# Schema_plan_b_syntheseproject_V1.net
KiCad netlist of a schematic drawn in EasyEDA
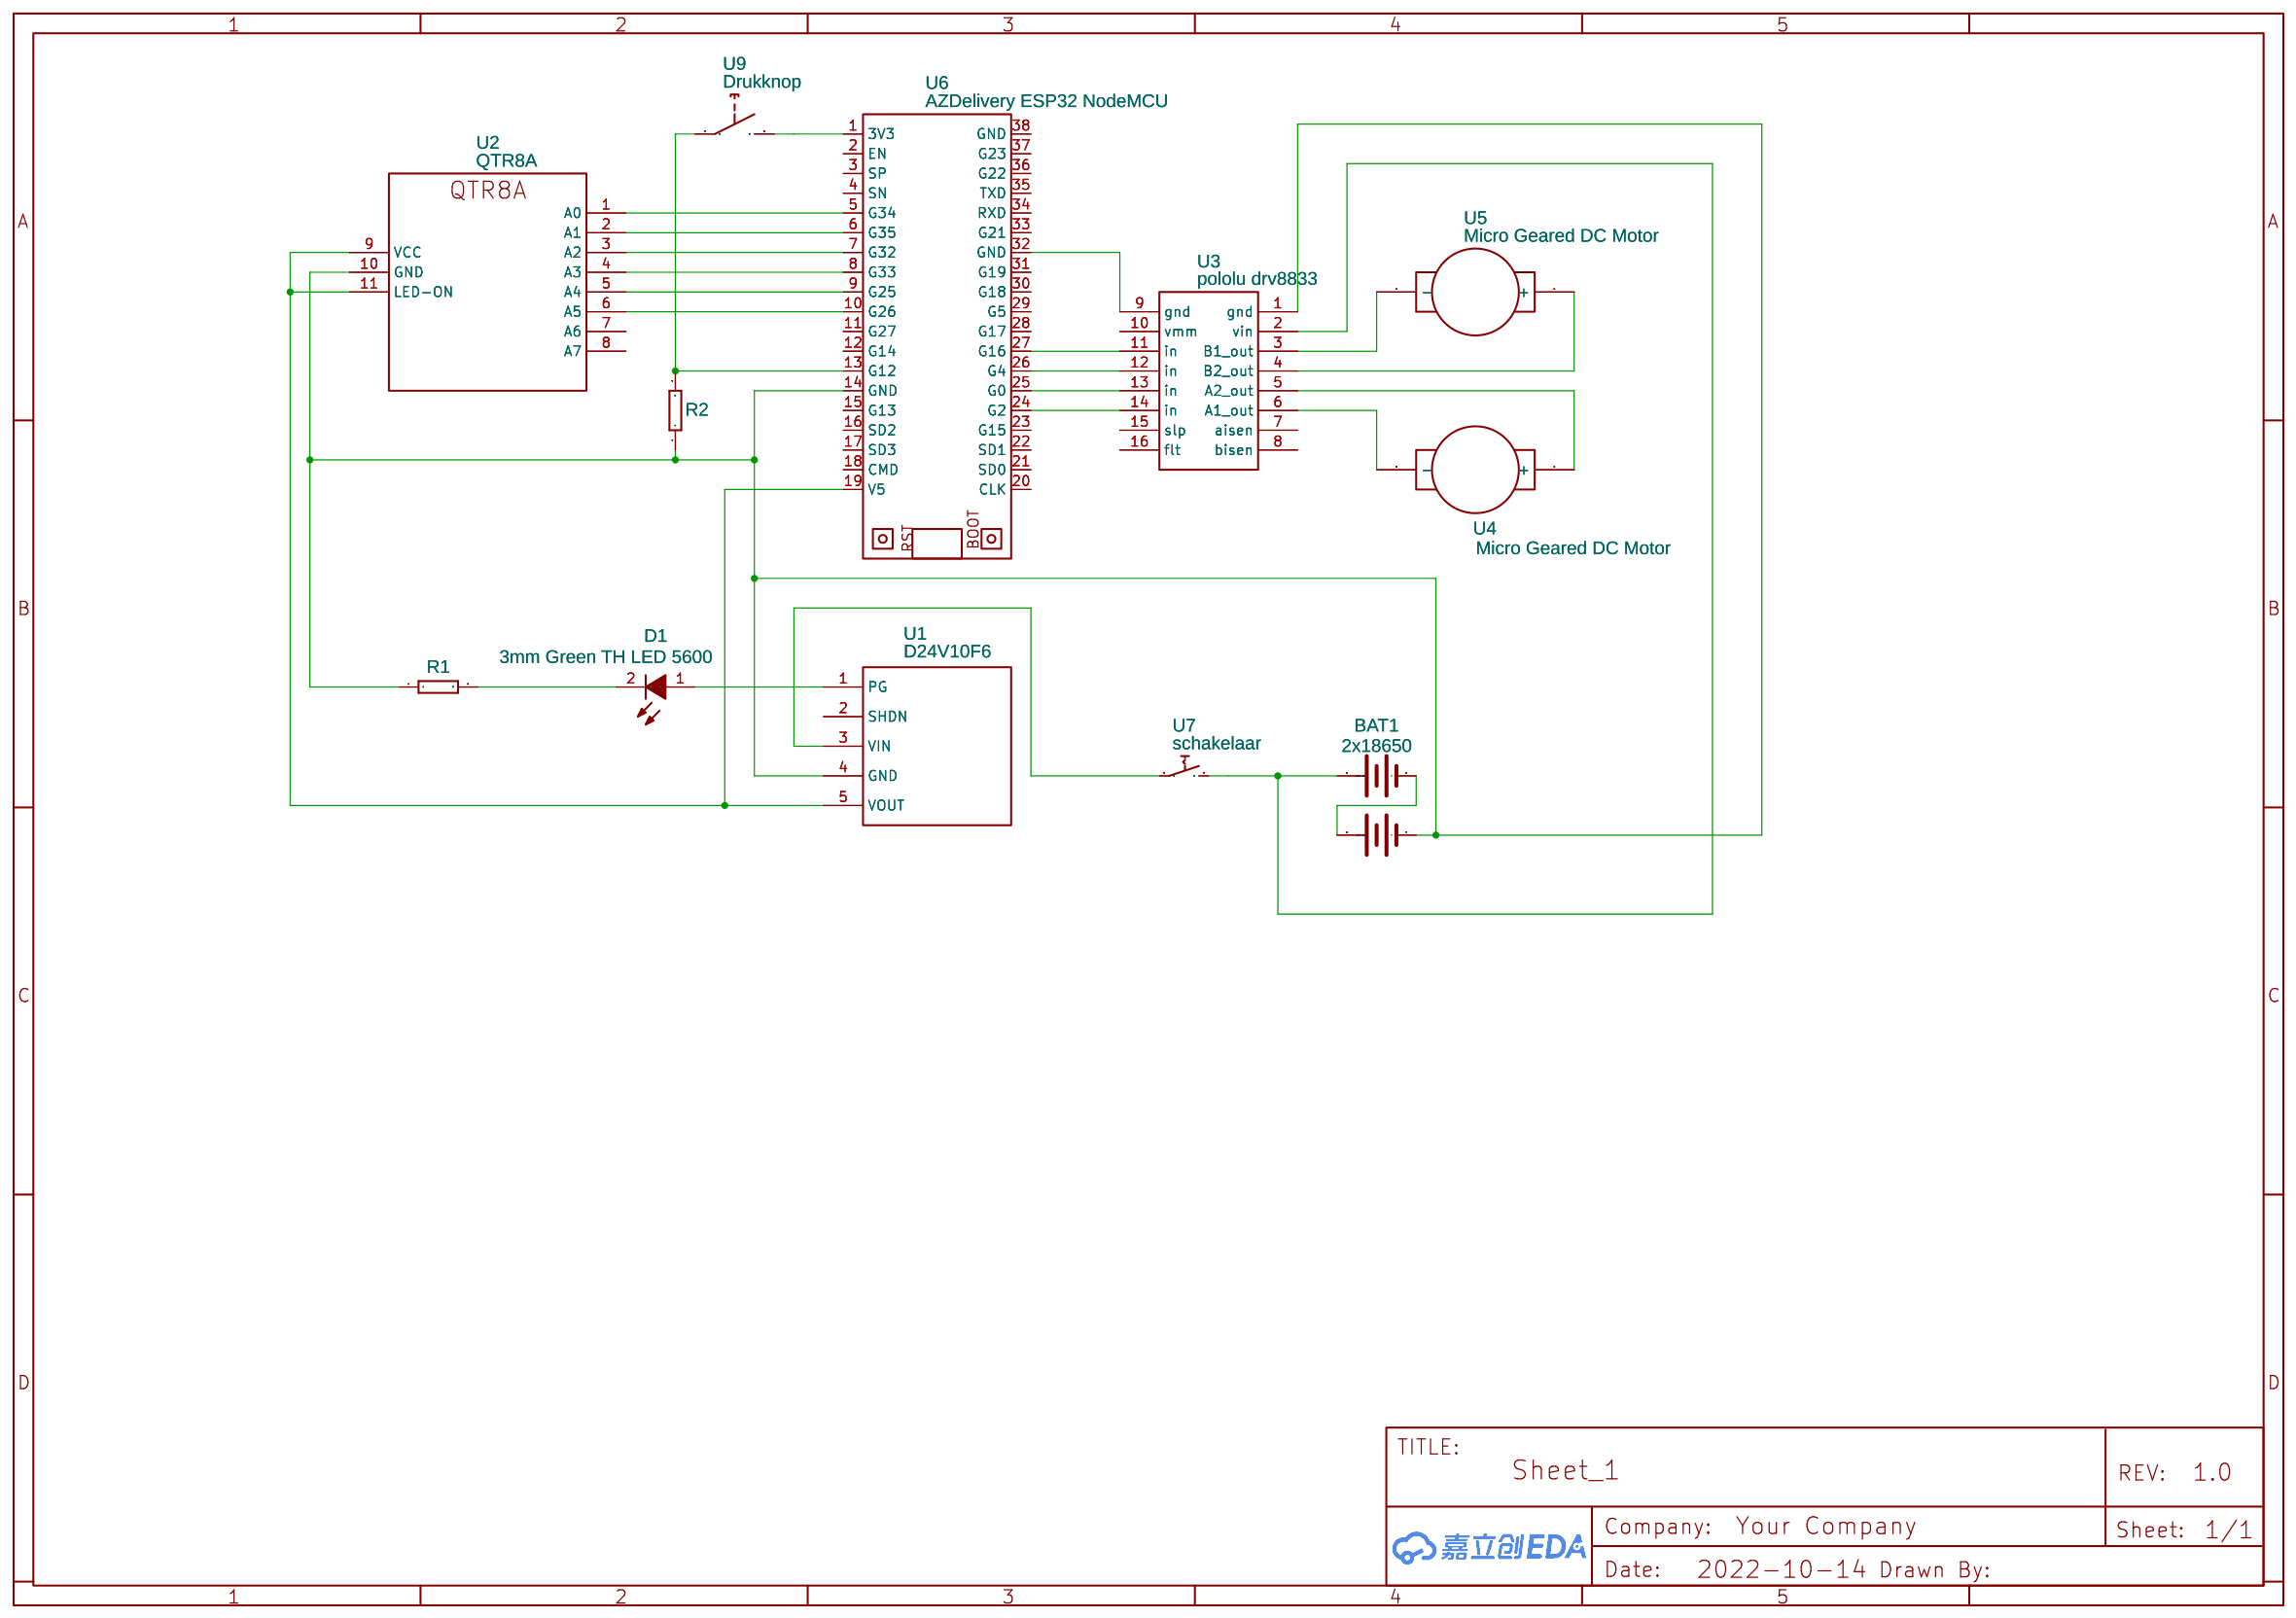
[diagram p0: schematic sheet]

(export (version "E")
  (design (tool "Eeschema 10.0.6"))
  (components
    (comp (ref "BAT1")
      (value "2x18650")
      (fields
        (field (name "BOM_Manufacturer Part") "18650并联电池盒")
        (field (name "BOM_Supplier Part") "C9900010344")
      )
      (libsource (lib "") (part "18650并联电池盒"))
    )
    (comp (ref "D1")
      (value "3mm Green TH LED 5600")
      (fields (field (name "BOM_Manufacturer Part") "5600") (field (name "BOM_Supplier Part") "L20325-ND"))
      (libsource (lib "") (part "3mm Green TH LED 5600"))
    )
    (comp (ref "R1") (value "RESISTOR-0402") (libsource (lib "") (part "RESISTOR-0402")))
    (comp (ref "R2") (value "RESISTOR-0402") (libsource (lib "") (part "RESISTOR-0402_1")))
    (comp (ref "U1")
      (value "D24V10F6")
      (fields (field (name "BOM_Manufacturer Part") "2832"))
      (libsource (lib "") (part "D24V10F6"))
    )
    (comp (ref "U2") (value "QTR8A") (libsource (lib "") (part "QTR8A")))
    (comp (ref "U3") (value "pololu drv8833") (libsource (lib "") (part "pololu drv8833")))
    (comp (ref "U4") (value "Micro Geared DC Motor") (libsource (lib "") (part "Micro Geared DC Motor")))
    (comp (ref "U5") (value "Micro Geared DC Motor") (libsource (lib "") (part "Micro Geared DC Motor")))
    (comp (ref "U6")
      (value "AZDelivery ESP32 NodeMCU")
      (fields (field (name "BOM_Supplier Part") "ESP32-WROOM-32"))
      (libsource (lib "") (part "AZDelivery ESP32 NodeMCU"))
    )
    (comp (ref "U7") (value "schakelaar") (libsource (lib "") (part "schakelaar")))
    (comp (ref "U9") (value "Drukknop") (libsource (lib "") (part "Drukknop")))
  )
  (nets
    (net (code "1") (name "Net-(BAT1-+-Pad2)") (class "Default")
      (node (ref "BAT1") (pin "2") (pinfunction "+_2") (pintype "passive"))
      (node (ref "BAT1") (pin "3") (pinfunction "-_3") (pintype "passive"))
    )
    (net (code "2") (name "Net-(D1-A)") (class "Default")
      (node (ref "D1") (pin "1") (pinfunction "A_1") (pintype "unspecified"))
      (node (ref "U1") (pin "1") (pinfunction "PG_1") (pintype "unspecified"))
    )
    (net (code "3") (name "Net-(D1-K)") (class "Default")
      (node (ref "D1") (pin "2") (pinfunction "K_2") (pintype "unspecified"))
      (node (ref "R1") (pin "2") (pinfunction "2_2") (pintype "unspecified"))
    )
    (net (code "4") (name "Net-(U1-GND)") (class "Default")
      (node (ref "BAT1") (pin "4") (pinfunction "-_4") (pintype "passive"))
      (node (ref "R1") (pin "1") (pinfunction "1_1") (pintype "unspecified"))
      (node (ref "R2") (pin "1") (pinfunction "1_1") (pintype "unspecified"))
      (node (ref "U1") (pin "4") (pinfunction "GND_4") (pintype "unspecified"))
      (node (ref "U2") (pin "10") (pinfunction "GND_10") (pintype "unspecified"))
      (node (ref "U3") (pin "1") (pinfunction "gnd_1") (pintype "unspecified"))
      (node (ref "U6") (pin "14") (pinfunction "GND_14") (pintype "unspecified"))
    )
    (net (code "5") (name "Net-(U1-VIN)") (class "Default")
      (node (ref "U1") (pin "3") (pinfunction "VIN_3") (pintype "unspecified"))
      (node (ref "U7") (pin "2") (pinfunction "2_2") (pintype "unspecified"))
    )
    (net (code "6") (name "Net-(U1-VOUT)") (class "Default")
      (node (ref "U1") (pin "5") (pinfunction "VOUT_5") (pintype "unspecified"))
      (node (ref "U2") (pin "11") (pinfunction "LED-ON_11") (pintype "unspecified"))
      (node (ref "U2") (pin "9") (pinfunction "VCC_9") (pintype "unspecified"))
      (node (ref "U6") (pin "19") (pinfunction "V5_19") (pintype "unspecified"))
    )
    (net (code "7") (name "Net-(U2-A0)") (class "Default")
      (node (ref "U2") (pin "1") (pinfunction "A0_1") (pintype "unspecified"))
      (node (ref "U6") (pin "5") (pinfunction "G34_5") (pintype "unspecified"))
    )
    (net (code "8") (name "Net-(U2-A1)") (class "Default")
      (node (ref "U2") (pin "2") (pinfunction "A1_2") (pintype "unspecified"))
      (node (ref "U6") (pin "6") (pinfunction "G35_6") (pintype "unspecified"))
    )
    (net (code "9") (name "Net-(U2-A2)") (class "Default")
      (node (ref "U2") (pin "3") (pinfunction "A2_3") (pintype "unspecified"))
      (node (ref "U6") (pin "7") (pinfunction "G32_7") (pintype "unspecified"))
    )
    (net (code "10") (name "Net-(U2-A3)") (class "Default")
      (node (ref "U2") (pin "4") (pinfunction "A3_4") (pintype "unspecified"))
      (node (ref "U6") (pin "8") (pinfunction "G33_8") (pintype "unspecified"))
    )
    (net (code "11") (name "Net-(U2-A4)") (class "Default")
      (node (ref "U2") (pin "5") (pinfunction "A4_5") (pintype "unspecified"))
      (node (ref "U6") (pin "9") (pinfunction "G25_9") (pintype "unspecified"))
    )
    (net (code "12") (name "Net-(U2-A5)") (class "Default")
      (node (ref "U2") (pin "6") (pinfunction "A5_6") (pintype "unspecified"))
      (node (ref "U6") (pin "10") (pinfunction "G26_10") (pintype "unspecified"))
    )
    (net (code "13") (name "Net-(U3-A1_out)") (class "Default")
      (node (ref "U3") (pin "6") (pinfunction "A1_out_6") (pintype "unspecified"))
      (node (ref "U4") (pin "1") (pinfunction "-_1") (pintype "unspecified"))
    )
    (net (code "14") (name "Net-(U3-A2_out)") (class "Default")
      (node (ref "U3") (pin "5") (pinfunction "A2_out_5") (pintype "unspecified"))
      (node (ref "U4") (pin "2") (pinfunction "+_2") (pintype "unspecified"))
    )
    (net (code "15") (name "Net-(U3-B1_out)") (class "Default")
      (node (ref "U3") (pin "3") (pinfunction "B1_out_3") (pintype "unspecified"))
      (node (ref "U5") (pin "1") (pinfunction "-_1") (pintype "unspecified"))
    )
    (net (code "16") (name "Net-(U3-B2_out)") (class "Default")
      (node (ref "U3") (pin "4") (pinfunction "B2_out_4") (pintype "unspecified"))
      (node (ref "U5") (pin "2") (pinfunction "+_2") (pintype "unspecified"))
    )
    (net (code "17") (name "Net-(U3-gnd-Pad9)") (class "Default")
      (node (ref "U3") (pin "9") (pinfunction "gnd_9") (pintype "unspecified"))
      (node (ref "U6") (pin "32") (pinfunction "GND_32") (pintype "unspecified"))
    )
    (net (code "18") (name "Net-(U3-vin)") (class "Default")
      (node (ref "BAT1") (pin "1") (pinfunction "+_1") (pintype "passive"))
      (node (ref "U3") (pin "2") (pinfunction "vin_2") (pintype "unspecified"))
      (node (ref "U7") (pin "1") (pinfunction "1_1") (pintype "unspecified"))
    )
    (net (code "19") (name "Net-(U6-3V3)") (class "Default")
      (node (ref "U6") (pin "1") (pinfunction "3V3_1") (pintype "unspecified"))
      (node (ref "U9") (pin "2") (pinfunction "2_2") (pintype "unspecified"))
    )
    (net (code "20") (name "Net-(U6-G0)") (class "Default")
      (node (ref "U3") (pin "13") (pinfunction "in_13") (pintype "unspecified"))
      (node (ref "U6") (pin "25") (pinfunction "G0_25") (pintype "unspecified"))
    )
    (net (code "21") (name "Net-(U6-G2)") (class "Default")
      (node (ref "U3") (pin "14") (pinfunction "in_14") (pintype "unspecified"))
      (node (ref "U6") (pin "24") (pinfunction "G2_24") (pintype "unspecified"))
    )
    (net (code "22") (name "Net-(U6-G4)") (class "Default")
      (node (ref "U3") (pin "12") (pinfunction "in_12") (pintype "unspecified"))
      (node (ref "U6") (pin "26") (pinfunction "G4_26") (pintype "unspecified"))
    )
    (net (code "23") (name "Net-(U6-G12)") (class "Default")
      (node (ref "R2") (pin "2") (pinfunction "2_2") (pintype "unspecified"))
      (node (ref "U6") (pin "13") (pinfunction "G12_13") (pintype "unspecified"))
      (node (ref "U9") (pin "1") (pinfunction "1_1") (pintype "unspecified"))
    )
    (net (code "24") (name "Net-(U6-G16)") (class "Default")
      (node (ref "U3") (pin "11") (pinfunction "in_11") (pintype "unspecified"))
      (node (ref "U6") (pin "27") (pinfunction "G16_27") (pintype "unspecified"))
    )
    (net (code "25") (name "unconnected-(U1-SHDN-Pad2)") (class "Default")
      (node (ref "U1") (pin "2") (pinfunction "SHDN_2") (pintype "unspecified"))
    )
    (net (code "26") (name "unconnected-(U2-A6-Pad7)") (class "Default")
      (node (ref "U2") (pin "7") (pinfunction "A6_7") (pintype "unspecified"))
    )
    (net (code "27") (name "unconnected-(U2-A7-Pad8)") (class "Default")
      (node (ref "U2") (pin "8") (pinfunction "A7_8") (pintype "unspecified"))
    )
    (net (code "28") (name "unconnected-(U3-aisen-Pad7)") (class "Default")
      (node (ref "U3") (pin "7") (pinfunction "aisen_7") (pintype "unspecified"))
    )
    (net (code "29") (name "unconnected-(U3-bisen-Pad8)") (class "Default")
      (node (ref "U3") (pin "8") (pinfunction "bisen_8") (pintype "unspecified"))
    )
    (net (code "30") (name "unconnected-(U3-flt-Pad16)") (class "Default")
      (node (ref "U3") (pin "16") (pinfunction "flt_16") (pintype "unspecified"))
    )
    (net (code "31") (name "unconnected-(U3-slp-Pad15)") (class "Default")
      (node (ref "U3") (pin "15") (pinfunction "slp_15") (pintype "unspecified"))
    )
    (net (code "32") (name "unconnected-(U3-vmm-Pad10)") (class "Default")
      (node (ref "U3") (pin "10") (pinfunction "vmm_10") (pintype "unspecified"))
    )
    (net (code "33") (name "unconnected-(U6-CLK-Pad20)") (class "Default")
      (node (ref "U6") (pin "20") (pinfunction "CLK_20") (pintype "unspecified"))
    )
    (net (code "34") (name "unconnected-(U6-CMD-Pad18)") (class "Default")
      (node (ref "U6") (pin "18") (pinfunction "CMD_18") (pintype "unspecified"))
    )
    (net (code "35") (name "unconnected-(U6-EN-Pad2)") (class "Default")
      (node (ref "U6") (pin "2") (pinfunction "EN_2") (pintype "unspecified"))
    )
    (net (code "36") (name "unconnected-(U6-G5-Pad29)") (class "Default")
      (node (ref "U6") (pin "29") (pinfunction "G5_29") (pintype "unspecified"))
    )
    (net (code "37") (name "unconnected-(U6-G13-Pad15)") (class "Default")
      (node (ref "U6") (pin "15") (pinfunction "G13_15") (pintype "unspecified"))
    )
    (net (code "38") (name "unconnected-(U6-G14-Pad12)") (class "Default")
      (node (ref "U6") (pin "12") (pinfunction "G14_12") (pintype "unspecified"))
    )
    (net (code "39") (name "unconnected-(U6-G15-Pad23)") (class "Default")
      (node (ref "U6") (pin "23") (pinfunction "G15_23") (pintype "unspecified"))
    )
    (net (code "40") (name "unconnected-(U6-G17-Pad28)") (class "Default")
      (node (ref "U6") (pin "28") (pinfunction "G17_28") (pintype "unspecified"))
    )
    (net (code "41") (name "unconnected-(U6-G18-Pad30)") (class "Default")
      (node (ref "U6") (pin "30") (pinfunction "G18_30") (pintype "unspecified"))
    )
    (net (code "42") (name "unconnected-(U6-G19-Pad31)") (class "Default")
      (node (ref "U6") (pin "31") (pinfunction "G19_31") (pintype "unspecified"))
    )
    (net (code "43") (name "unconnected-(U6-G21-Pad33)") (class "Default")
      (node (ref "U6") (pin "33") (pinfunction "G21_33") (pintype "unspecified"))
    )
    (net (code "44") (name "unconnected-(U6-G22-Pad36)") (class "Default")
      (node (ref "U6") (pin "36") (pinfunction "G22_36") (pintype "unspecified"))
    )
    (net (code "45") (name "unconnected-(U6-G23-Pad37)") (class "Default")
      (node (ref "U6") (pin "37") (pinfunction "G23_37") (pintype "unspecified"))
    )
    (net (code "46") (name "unconnected-(U6-G27-Pad11)") (class "Default")
      (node (ref "U6") (pin "11") (pinfunction "G27_11") (pintype "unspecified"))
    )
    (net (code "47") (name "unconnected-(U6-GND-Pad38)") (class "Default")
      (node (ref "U6") (pin "38") (pinfunction "GND_38") (pintype "unspecified"))
    )
    (net (code "48") (name "unconnected-(U6-RXD-Pad34)") (class "Default")
      (node (ref "U6") (pin "34") (pinfunction "RXD_34") (pintype "unspecified"))
    )
    (net (code "49") (name "unconnected-(U6-SD0-Pad21)") (class "Default")
      (node (ref "U6") (pin "21") (pinfunction "SD0_21") (pintype "unspecified"))
    )
    (net (code "50") (name "unconnected-(U6-SD1-Pad22)") (class "Default")
      (node (ref "U6") (pin "22") (pinfunction "SD1_22") (pintype "unspecified"))
    )
    (net (code "51") (name "unconnected-(U6-SD2-Pad16)") (class "Default")
      (node (ref "U6") (pin "16") (pinfunction "SD2_16") (pintype "unspecified"))
    )
    (net (code "52") (name "unconnected-(U6-SD3-Pad17)") (class "Default")
      (node (ref "U6") (pin "17") (pinfunction "SD3_17") (pintype "unspecified"))
    )
    (net (code "53") (name "unconnected-(U6-SN-Pad4)") (class "Default")
      (node (ref "U6") (pin "4") (pinfunction "SN_4") (pintype "unspecified"))
    )
    (net (code "54") (name "unconnected-(U6-SP-Pad3)") (class "Default")
      (node (ref "U6") (pin "3") (pinfunction "SP_3") (pintype "unspecified"))
    )
    (net (code "55") (name "unconnected-(U6-TXD-Pad35)") (class "Default")
      (node (ref "U6") (pin "35") (pinfunction "TXD_35") (pintype "unspecified"))
    )
  )
)
